# FTDI_Basic-5V.net
KiCad netlist of a schematic drawn in EAGLE
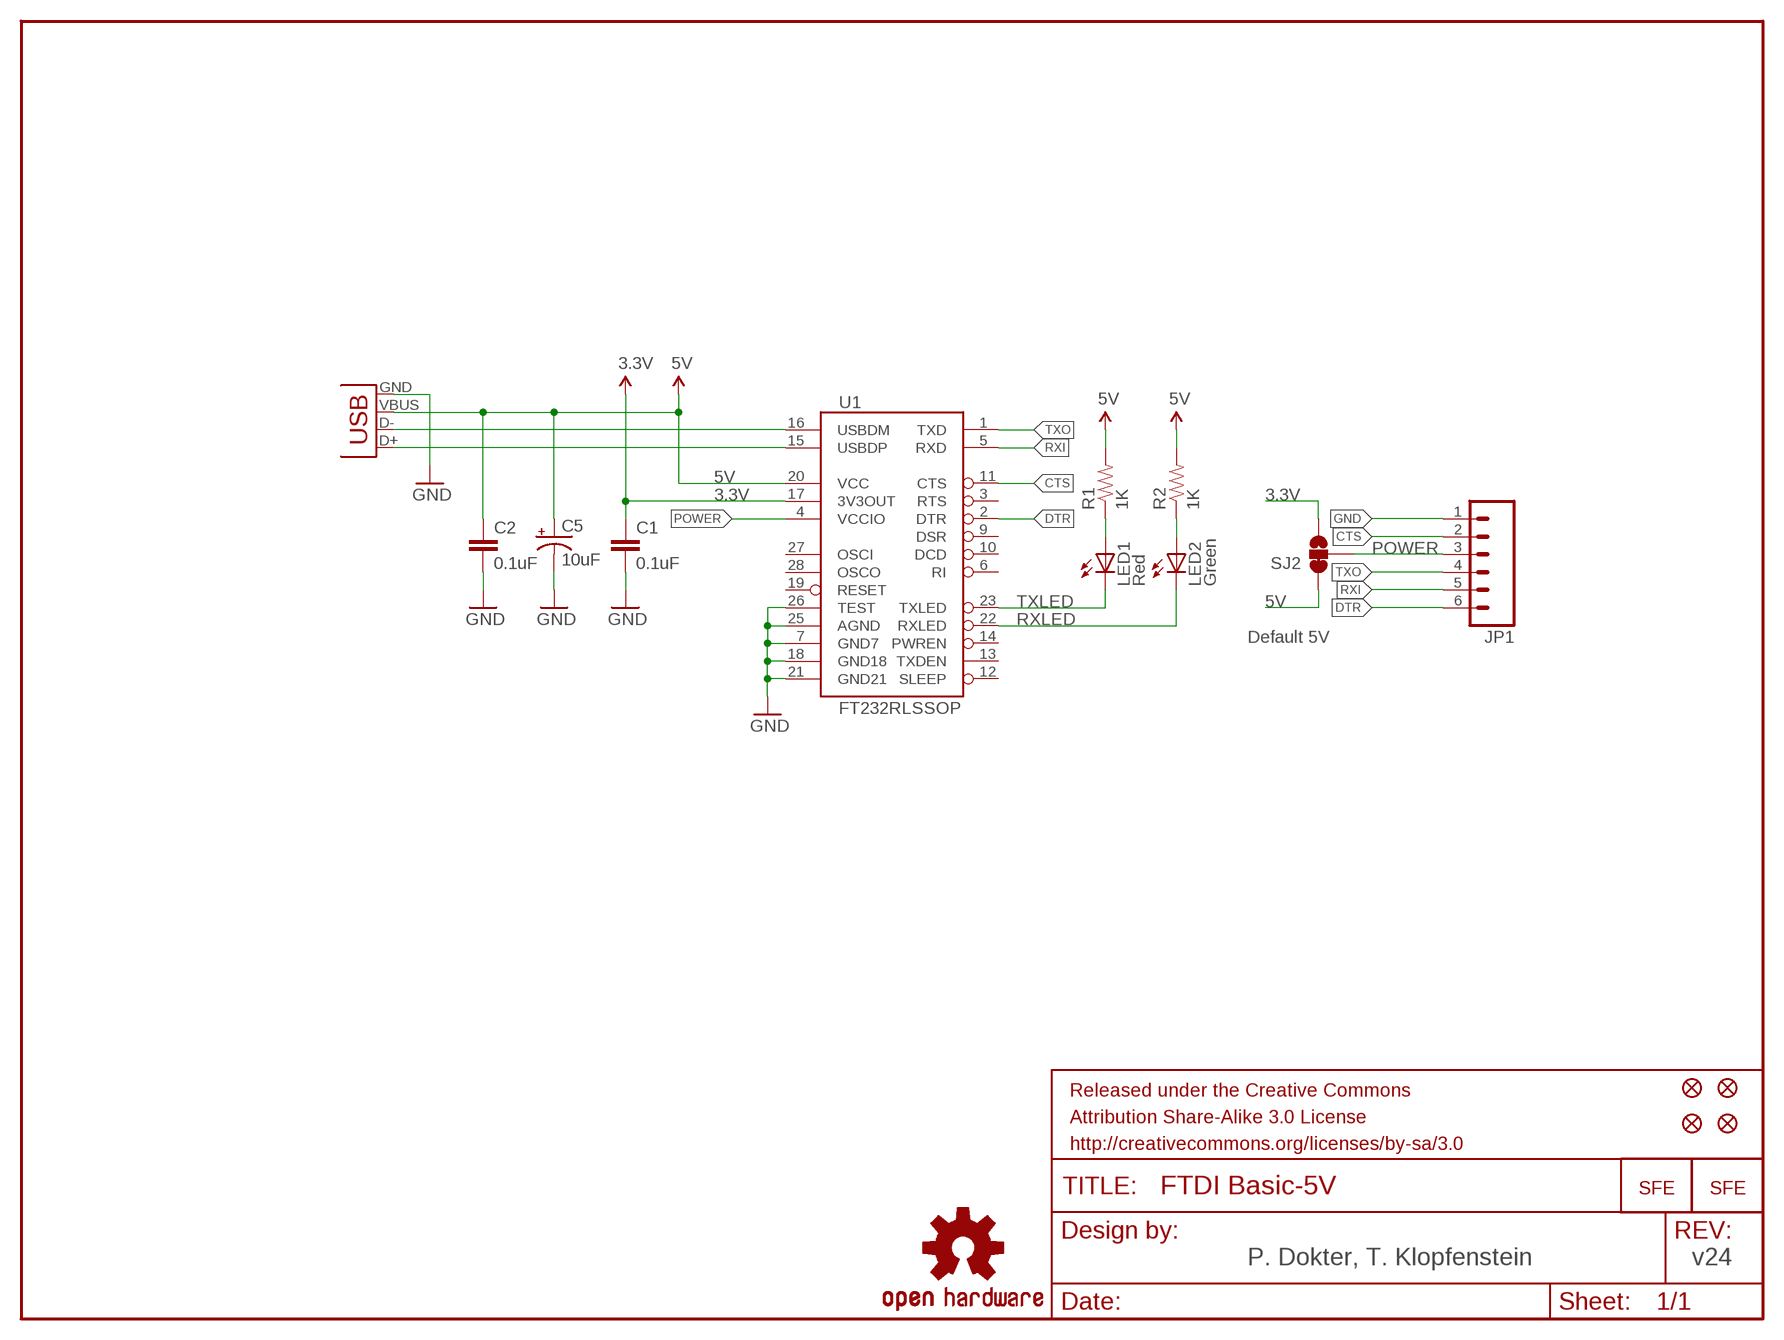
[diagram p0: schematic, sheet 1]

(export (version "E")
  (design (tool "Eeschema 10.0.6"))
  (components
    (comp (ref "C1")
      (value "0.1uF")
      (footprint "eagle-import:0603-CAP")
      (libsource (lib "eagle-import") (part "CAP0603-CAP"))
    )
    (comp (ref "C2")
      (value "0.1uF")
      (footprint "eagle-import:0603-CAP")
      (libsource (lib "eagle-import") (part "CAP0603-CAP"))
    )
    (comp (ref "C5")
      (value "10uF")
      (footprint "eagle-import:EIA3216")
      (libsource (lib "eagle-import") (part "CAP_POL1206"))
    )
    (comp (ref "FRAME1")
      (value "FRAME-LETTER")
      (footprint "eagle-import:CREATIVE_COMMONS")
      (libsource (lib "eagle-import") (part "FRAME-LETTER"))
    )
    (comp (ref "JP1")
      (value "M06SMD-FEMALE-V2")
      (footprint "eagle-import:1X06-SMD-FEMALE-V2")
      (libsource (lib "eagle-import") (part "M06SMD-FEMALE-V2"))
    )
    (comp (ref "JP2")
      (value "LOGO-SFESK")
      (footprint "eagle-import:SFE-LOGO-FLAME")
      (libsource (lib "eagle-import") (part "LOGO-SFESK"))
    )
    (comp (ref "JP3")
      (value "FIDUCIAL1X2")
      (footprint "eagle-import:FIDUCIAL-1X2")
      (libsource (lib "eagle-import") (part "FIDUCIAL1X2"))
    )
    (comp (ref "JP4")
      (value "FIDUCIAL1X2")
      (footprint "eagle-import:FIDUCIAL-1X2")
      (libsource (lib "eagle-import") (part "FIDUCIAL1X2"))
    )
    (comp (ref "JP5")
      (value "FIDUCIAL1X2")
      (footprint "eagle-import:FIDUCIAL-1X2")
      (libsource (lib "eagle-import") (part "FIDUCIAL1X2"))
    )
    (comp (ref "JP6")
      (value "FIDUCIAL1X2")
      (footprint "eagle-import:FIDUCIAL-1X2")
      (libsource (lib "eagle-import") (part "FIDUCIAL1X2"))
    )
    (comp (ref "LED1")
      (value "Red")
      (footprint "eagle-import:LED-0603")
      (libsource (lib "eagle-import") (part "LED0603"))
    )
    (comp (ref "LED2")
      (value "Green")
      (footprint "eagle-import:LED-0603")
      (libsource (lib "eagle-import") (part "LED0603"))
    )
    (comp (ref "LOGO1")
      (value "OSHW-LOGOS")
      (footprint "eagle-import:OSHW-LOGO-S")
      (libsource (lib "eagle-import") (part "OSHW-LOGOS"))
    )
    (comp (ref "R1")
      (value "1K")
      (footprint "eagle-import:0603-RES")
      (libsource (lib "eagle-import") (part "RESISTOR0603-RES"))
    )
    (comp (ref "R2")
      (value "1K")
      (footprint "eagle-import:0603-RES")
      (libsource (lib "eagle-import") (part "RESISTOR0603-RES"))
    )
    (comp (ref "SJ2")
      (value "SOLDERJUMPER_2WAYS")
      (footprint "eagle-import:SJ_3")
      (libsource (lib "eagle-import") (part "SOLDERJUMPER_2WAYS"))
    )
    (comp (ref "U$2")
      (value "LOGO-SFENW2")
      (footprint "eagle-import:SFE-NEW-WEB")
      (libsource (lib "eagle-import") (part "LOGO-SFENW2"))
    )
    (comp (ref "U1")
      (value "FT232RLSSOP")
      (footprint "eagle-import:SSOP28DB")
      (libsource (lib "eagle-import") (part "FT232RLSSOP"))
    )
    (comp (ref "X2")
      (value "USB-SMD-NS")
      (footprint "eagle-import:USB-MINIB-NOSTOP")
      (libsource (lib "eagle-import") (part "USB-SMD-NS"))
    )
  )
  (nets
    (net (code "1") (name "/RXLED") (class "Default")
      (node (ref "LED2") (pin "C") (pinfunction "C_C") (pintype "passive"))
      (node (ref "U1") (pin "22") (pinfunction "RXLED_22") (pintype "input"))
    )
    (net (code "2") (name "/TXLED") (class "Default")
      (node (ref "LED1") (pin "C") (pinfunction "C_C") (pintype "passive"))
      (node (ref "U1") (pin "23") (pinfunction "TXLED_23") (pintype "input"))
    )
    (net (code "3") (name "3.3V") (class "Default")
      (node (ref "C1") (pin "1") (pinfunction "1_1") (pintype "passive"))
      (node (ref "SJ2") (pin "3") (pinfunction "3_3") (pintype "passive"))
      (node (ref "U1") (pin "17") (pinfunction "3V3OUT_17") (pintype "output"))
    )
    (net (code "4") (name "5V") (class "Default")
      (node (ref "C2") (pin "1") (pinfunction "1_1") (pintype "passive"))
      (node (ref "C5") (pin "A") (pinfunction "+_A") (pintype "passive"))
      (node (ref "R1") (pin "2") (pinfunction "2_2") (pintype "passive"))
      (node (ref "R2") (pin "2") (pinfunction "2_2") (pintype "passive"))
      (node (ref "SJ2") (pin "1") (pinfunction "1_1") (pintype "passive"))
      (node (ref "U1") (pin "20") (pinfunction "VCC_20") (pintype "power_in"))
      (node (ref "X2") (pin "VBUS") (pinfunction "VBUS_VBUS") (pintype "bidirectional"))
    )
    (net (code "5") (name "CTS") (class "Default")
      (node (ref "JP1") (pin "2") (pinfunction "2_2") (pintype "passive"))
      (node (ref "U1") (pin "11") (pinfunction "CTS_11") (pintype "input"))
    )
    (net (code "6") (name "DTR") (class "Default")
      (node (ref "JP1") (pin "6") (pinfunction "6_6") (pintype "passive"))
      (node (ref "U1") (pin "2") (pinfunction "DTR_2") (pintype "output"))
    )
    (net (code "7") (name "GND") (class "Default")
      (node (ref "C1") (pin "2") (pinfunction "2_2") (pintype "passive"))
      (node (ref "C2") (pin "2") (pinfunction "2_2") (pintype "passive"))
      (node (ref "C5") (pin "C") (pinfunction "-_C") (pintype "passive"))
      (node (ref "JP1") (pin "1") (pinfunction "1_1") (pintype "passive"))
      (node (ref "U1") (pin "18") (pinfunction "GND18_18") (pintype "power_in"))
      (node (ref "U1") (pin "21") (pinfunction "GND21_21") (pintype "power_in"))
      (node (ref "U1") (pin "25") (pinfunction "AGND_25") (pintype "power_in"))
      (node (ref "U1") (pin "26") (pinfunction "TEST_26") (pintype "input"))
      (node (ref "U1") (pin "7") (pinfunction "GND7_7") (pintype "power_in"))
      (node (ref "X2") (pin "GND") (pinfunction "GND_GND") (pintype "bidirectional"))
    )
    (net (code "8") (name "Net-(LED1-PadA)") (class "Default")
      (node (ref "LED1") (pin "A") (pinfunction "A_A") (pintype "passive"))
      (node (ref "R1") (pin "1") (pinfunction "1_1") (pintype "passive"))
    )
    (net (code "9") (name "Net-(LED2-PadA)") (class "Default")
      (node (ref "LED2") (pin "A") (pinfunction "A_A") (pintype "passive"))
      (node (ref "R2") (pin "1") (pinfunction "1_1") (pintype "passive"))
    )
    (net (code "10") (name "Net-(U1-USBDM)") (class "Default")
      (node (ref "U1") (pin "16") (pinfunction "USBDM_16") (pintype "bidirectional"))
      (node (ref "X2") (pin "D-") (pinfunction "D-_D-") (pintype "bidirectional"))
    )
    (net (code "11") (name "Net-(U1-USBDP)") (class "Default")
      (node (ref "U1") (pin "15") (pinfunction "USBDP_15") (pintype "bidirectional"))
      (node (ref "X2") (pin "D+") (pinfunction "D+_D+") (pintype "bidirectional"))
    )
    (net (code "12") (name "POWER") (class "Default")
      (node (ref "JP1") (pin "3") (pinfunction "3_3") (pintype "passive"))
      (node (ref "SJ2") (pin "2") (pinfunction "2_2") (pintype "passive"))
      (node (ref "U1") (pin "4") (pinfunction "VCCIO_4") (pintype "power_in"))
    )
    (net (code "13") (name "RXI") (class "Default")
      (node (ref "JP1") (pin "5") (pinfunction "5_5") (pintype "passive"))
      (node (ref "U1") (pin "5") (pinfunction "RXD_5") (pintype "input"))
    )
    (net (code "14") (name "TXO") (class "Default")
      (node (ref "JP1") (pin "4") (pinfunction "4_4") (pintype "passive"))
      (node (ref "U1") (pin "1") (pinfunction "TXD_1") (pintype "output"))
    )
    (net (code "15") (name "unconnected-(U1-DCD-Pad10)") (class "Default")
      (node (ref "U1") (pin "10") (pinfunction "DCD_10") (pintype "input"))
    )
    (net (code "16") (name "unconnected-(U1-DSR-Pad9)") (class "Default")
      (node (ref "U1") (pin "9") (pinfunction "DSR_9") (pintype "input"))
    )
    (net (code "17") (name "unconnected-(U1-OSCI-Pad27)") (class "Default")
      (node (ref "U1") (pin "27") (pinfunction "OSCI_27") (pintype "input"))
    )
    (net (code "18") (name "unconnected-(U1-OSCO-Pad28)") (class "Default")
      (node (ref "U1") (pin "28") (pinfunction "OSCO_28") (pintype "output"))
    )
    (net (code "19") (name "unconnected-(U1-PWREN-Pad14)") (class "Default")
      (node (ref "U1") (pin "14") (pinfunction "PWREN_14") (pintype "input"))
    )
    (net (code "20") (name "unconnected-(U1-RESET-Pad19)") (class "Default")
      (node (ref "U1") (pin "19") (pinfunction "RESET_19") (pintype "input"))
    )
    (net (code "21") (name "unconnected-(U1-RI-Pad6)") (class "Default")
      (node (ref "U1") (pin "6") (pinfunction "RI_6") (pintype "input"))
    )
    (net (code "22") (name "unconnected-(U1-RTS-Pad3)") (class "Default")
      (node (ref "U1") (pin "3") (pinfunction "RTS_3") (pintype "output"))
    )
    (net (code "23") (name "unconnected-(U1-SLEEP-Pad12)") (class "Default")
      (node (ref "U1") (pin "12") (pinfunction "SLEEP_12") (pintype "input"))
    )
    (net (code "24") (name "unconnected-(U1-TXDEN-Pad13)") (class "Default")
      (node (ref "U1") (pin "13") (pinfunction "TXDEN_13") (pintype "input"))
    )
  )
)
